# VisSleepSchema.net
KiCad netlist of a schematic drawn in EAGLE
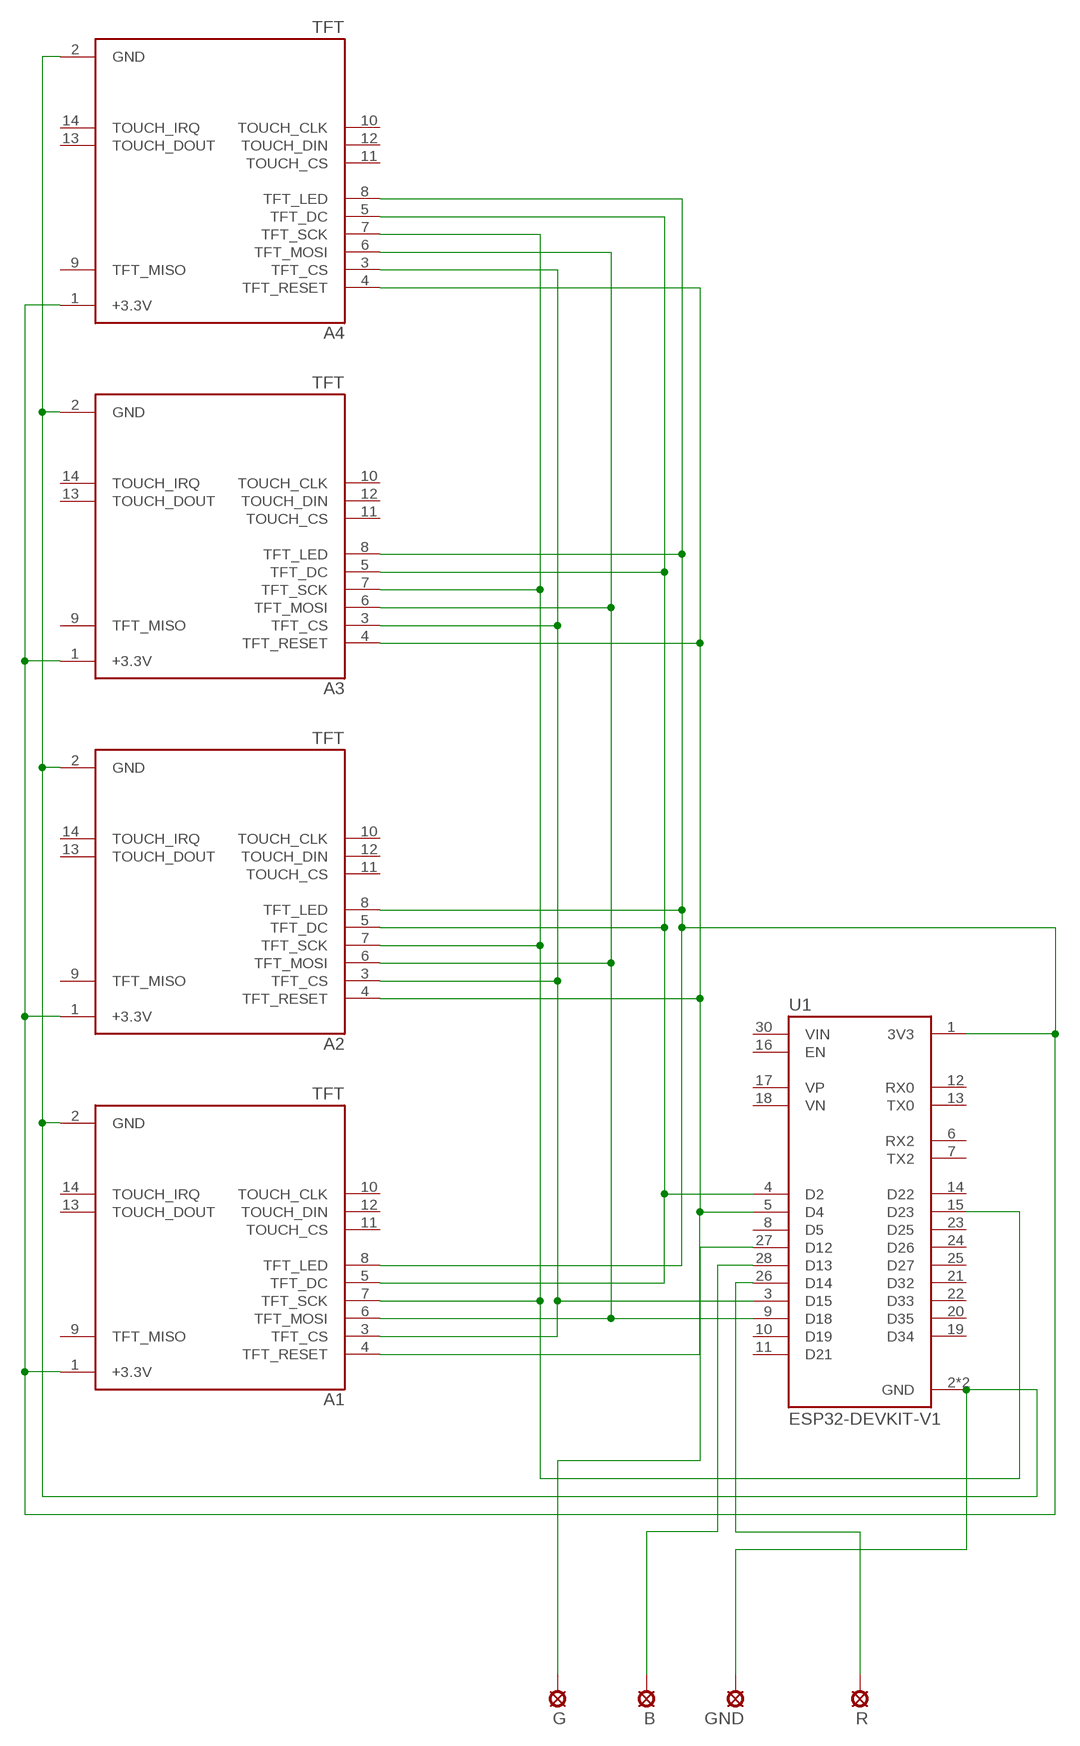
[diagram p0: schematic, sheet 1]

(export (version "E")
  (design (tool "Eeschema 10.0.6"))
  (components
    (comp (ref "A1")
      (value "TFT")
      (footprint "eagle-import:2.8_LCD")
      (libsource (lib "eagle-import") (part "TFT"))
    )
    (comp (ref "A2")
      (value "TFT")
      (footprint "eagle-import:2.8_LCD")
      (libsource (lib "eagle-import") (part "TFT"))
    )
    (comp (ref "A3")
      (value "TFT")
      (footprint "eagle-import:2.8_LCD")
      (libsource (lib "eagle-import") (part "TFT"))
    )
    (comp (ref "A4")
      (value "TFT")
      (footprint "eagle-import:2.8_LCD")
      (libsource (lib "eagle-import") (part "TFT"))
    )
    (comp (ref "B")
      (value "LSP10")
      (footprint "eagle-import:LSP10")
      (libsource (lib "eagle-import") (part "LSP10"))
    )
    (comp (ref "G")
      (value "LSP10")
      (footprint "eagle-import:LSP10")
      (libsource (lib "eagle-import") (part "LSP10"))
    )
    (comp (ref "GND")
      (value "LSP10")
      (footprint "eagle-import:LSP10")
      (libsource (lib "eagle-import") (part "LSP10"))
    )
    (comp (ref "R")
      (value "LSP10")
      (footprint "eagle-import:LSP10")
      (libsource (lib "eagle-import") (part "LSP10"))
    )
    (comp (ref "U1")
      (value "ESP32-DEVKIT-V1")
      (footprint "eagle-import:MODULE_ESP32_DEVKIT_V1")
      (fields (field (name "MF") "Do it"))
      (libsource (lib "eagle-import") (part "ESP32-DEVKIT-V1"))
    )
  )
  (nets
    (net (code "1") (name "Net-(A1-+3.3V)") (class "Default")
      (node (ref "A1") (pin "1") (pinfunction "+3.3V_1") (pintype "passive"))
      (node (ref "A1") (pin "8") (pinfunction "TFT_LED_8") (pintype "input"))
      (node (ref "A2") (pin "1") (pinfunction "+3.3V_1") (pintype "passive"))
      (node (ref "A2") (pin "8") (pinfunction "TFT_LED_8") (pintype "input"))
      (node (ref "A3") (pin "1") (pinfunction "+3.3V_1") (pintype "passive"))
      (node (ref "A3") (pin "8") (pinfunction "TFT_LED_8") (pintype "input"))
      (node (ref "A4") (pin "1") (pinfunction "+3.3V_1") (pintype "passive"))
      (node (ref "A4") (pin "8") (pinfunction "TFT_LED_8") (pintype "input"))
      (node (ref "U1") (pin "1") (pinfunction "3V3_1") (pintype "output"))
    )
    (net (code "2") (name "Net-(A1-GND)") (class "Default")
      (node (ref "A1") (pin "2") (pinfunction "GND_2") (pintype "passive"))
      (node (ref "A2") (pin "2") (pinfunction "GND_2") (pintype "passive"))
      (node (ref "A3") (pin "2") (pinfunction "GND_2") (pintype "passive"))
      (node (ref "A4") (pin "2") (pinfunction "GND_2") (pintype "passive"))
      (node (ref "GND") (pin "MP") (pinfunction "MP_MP") (pintype "passive"))
      (node (ref "U1") (pin "2") (pinfunction "GND_2") (pintype "power_in"))
      (node (ref "U1") (pin "29") (pinfunction "GND_29") (pintype "power_in"))
    )
    (net (code "3") (name "Net-(A1-TFT_CS)") (class "Default")
      (node (ref "A1") (pin "3") (pinfunction "TFT_CS_3") (pintype "input"))
      (node (ref "A2") (pin "3") (pinfunction "TFT_CS_3") (pintype "input"))
      (node (ref "A3") (pin "3") (pinfunction "TFT_CS_3") (pintype "input"))
      (node (ref "A4") (pin "3") (pinfunction "TFT_CS_3") (pintype "input"))
      (node (ref "U1") (pin "3") (pinfunction "D15_3") (pintype "bidirectional"))
    )
    (net (code "4") (name "Net-(A1-TFT_DC)") (class "Default")
      (node (ref "A1") (pin "5") (pinfunction "TFT_DC_5") (pintype "input"))
      (node (ref "A2") (pin "5") (pinfunction "TFT_DC_5") (pintype "input"))
      (node (ref "A3") (pin "5") (pinfunction "TFT_DC_5") (pintype "input"))
      (node (ref "A4") (pin "5") (pinfunction "TFT_DC_5") (pintype "input"))
      (node (ref "U1") (pin "4") (pinfunction "D2_4") (pintype "bidirectional"))
    )
    (net (code "5") (name "Net-(A1-TFT_MOSI)") (class "Default")
      (node (ref "A1") (pin "6") (pinfunction "TFT_MOSI_6") (pintype "input"))
      (node (ref "A2") (pin "6") (pinfunction "TFT_MOSI_6") (pintype "input"))
      (node (ref "A3") (pin "6") (pinfunction "TFT_MOSI_6") (pintype "input"))
      (node (ref "A4") (pin "6") (pinfunction "TFT_MOSI_6") (pintype "input"))
      (node (ref "U1") (pin "9") (pinfunction "D18_9") (pintype "bidirectional"))
    )
    (net (code "6") (name "Net-(A1-TFT_RESET)") (class "Default")
      (node (ref "A1") (pin "4") (pinfunction "TFT_RESET_4") (pintype "input"))
      (node (ref "A2") (pin "4") (pinfunction "TFT_RESET_4") (pintype "input"))
      (node (ref "A3") (pin "4") (pinfunction "TFT_RESET_4") (pintype "input"))
      (node (ref "A4") (pin "4") (pinfunction "TFT_RESET_4") (pintype "input"))
      (node (ref "U1") (pin "5") (pinfunction "D4_5") (pintype "bidirectional"))
    )
    (net (code "7") (name "Net-(A1-TFT_SCK)") (class "Default")
      (node (ref "A1") (pin "7") (pinfunction "TFT_SCK_7") (pintype "input"))
      (node (ref "A2") (pin "7") (pinfunction "TFT_SCK_7") (pintype "input"))
      (node (ref "A3") (pin "7") (pinfunction "TFT_SCK_7") (pintype "input"))
      (node (ref "A4") (pin "7") (pinfunction "TFT_SCK_7") (pintype "input"))
      (node (ref "U1") (pin "15") (pinfunction "D23_15") (pintype "bidirectional"))
    )
    (net (code "8") (name "Net-(U1-D12)") (class "Default")
      (node (ref "G") (pin "MP") (pinfunction "MP_MP") (pintype "passive"))
      (node (ref "U1") (pin "27") (pinfunction "D12_27") (pintype "bidirectional"))
    )
    (net (code "9") (name "Net-(U1-D13)") (class "Default")
      (node (ref "B") (pin "MP") (pinfunction "MP_MP") (pintype "passive"))
      (node (ref "U1") (pin "28") (pinfunction "D13_28") (pintype "bidirectional"))
    )
    (net (code "10") (name "Net-(U1-D14)") (class "Default")
      (node (ref "R") (pin "MP") (pinfunction "MP_MP") (pintype "passive"))
      (node (ref "U1") (pin "26") (pinfunction "D14_26") (pintype "bidirectional"))
    )
    (net (code "11") (name "unconnected-(A1-TFT_MISO-Pad9)") (class "Default")
      (node (ref "A1") (pin "9") (pinfunction "TFT_MISO_9") (pintype "tri_state"))
    )
    (net (code "12") (name "unconnected-(A1-TOUCH_CLK-Pad10)") (class "Default")
      (node (ref "A1") (pin "10") (pinfunction "TOUCH_CLK_10") (pintype "input"))
    )
    (net (code "13") (name "unconnected-(A1-TOUCH_CS-Pad11)") (class "Default")
      (node (ref "A1") (pin "11") (pinfunction "TOUCH_CS_11") (pintype "input"))
    )
    (net (code "14") (name "unconnected-(A1-TOUCH_DIN-Pad12)") (class "Default")
      (node (ref "A1") (pin "12") (pinfunction "TOUCH_DIN_12") (pintype "input"))
    )
    (net (code "15") (name "unconnected-(A1-TOUCH_DOUT-Pad13)") (class "Default")
      (node (ref "A1") (pin "13") (pinfunction "TOUCH_DOUT_13") (pintype "tri_state"))
    )
    (net (code "16") (name "unconnected-(A1-TOUCH_IRQ-Pad14)") (class "Default")
      (node (ref "A1") (pin "14") (pinfunction "TOUCH_IRQ_14") (pintype "open_collector"))
    )
    (net (code "17") (name "unconnected-(A2-TFT_MISO-Pad9)") (class "Default")
      (node (ref "A2") (pin "9") (pinfunction "TFT_MISO_9") (pintype "tri_state"))
    )
    (net (code "18") (name "unconnected-(A2-TOUCH_CLK-Pad10)") (class "Default")
      (node (ref "A2") (pin "10") (pinfunction "TOUCH_CLK_10") (pintype "input"))
    )
    (net (code "19") (name "unconnected-(A2-TOUCH_CS-Pad11)") (class "Default")
      (node (ref "A2") (pin "11") (pinfunction "TOUCH_CS_11") (pintype "input"))
    )
    (net (code "20") (name "unconnected-(A2-TOUCH_DIN-Pad12)") (class "Default")
      (node (ref "A2") (pin "12") (pinfunction "TOUCH_DIN_12") (pintype "input"))
    )
    (net (code "21") (name "unconnected-(A2-TOUCH_DOUT-Pad13)") (class "Default")
      (node (ref "A2") (pin "13") (pinfunction "TOUCH_DOUT_13") (pintype "tri_state"))
    )
    (net (code "22") (name "unconnected-(A2-TOUCH_IRQ-Pad14)") (class "Default")
      (node (ref "A2") (pin "14") (pinfunction "TOUCH_IRQ_14") (pintype "open_collector"))
    )
    (net (code "23") (name "unconnected-(A3-TFT_MISO-Pad9)") (class "Default")
      (node (ref "A3") (pin "9") (pinfunction "TFT_MISO_9") (pintype "tri_state"))
    )
    (net (code "24") (name "unconnected-(A3-TOUCH_CLK-Pad10)") (class "Default")
      (node (ref "A3") (pin "10") (pinfunction "TOUCH_CLK_10") (pintype "input"))
    )
    (net (code "25") (name "unconnected-(A3-TOUCH_CS-Pad11)") (class "Default")
      (node (ref "A3") (pin "11") (pinfunction "TOUCH_CS_11") (pintype "input"))
    )
    (net (code "26") (name "unconnected-(A3-TOUCH_DIN-Pad12)") (class "Default")
      (node (ref "A3") (pin "12") (pinfunction "TOUCH_DIN_12") (pintype "input"))
    )
    (net (code "27") (name "unconnected-(A3-TOUCH_DOUT-Pad13)") (class "Default")
      (node (ref "A3") (pin "13") (pinfunction "TOUCH_DOUT_13") (pintype "tri_state"))
    )
    (net (code "28") (name "unconnected-(A3-TOUCH_IRQ-Pad14)") (class "Default")
      (node (ref "A3") (pin "14") (pinfunction "TOUCH_IRQ_14") (pintype "open_collector"))
    )
    (net (code "29") (name "unconnected-(A4-TFT_MISO-Pad9)") (class "Default")
      (node (ref "A4") (pin "9") (pinfunction "TFT_MISO_9") (pintype "tri_state"))
    )
    (net (code "30") (name "unconnected-(A4-TOUCH_CLK-Pad10)") (class "Default")
      (node (ref "A4") (pin "10") (pinfunction "TOUCH_CLK_10") (pintype "input"))
    )
    (net (code "31") (name "unconnected-(A4-TOUCH_CS-Pad11)") (class "Default")
      (node (ref "A4") (pin "11") (pinfunction "TOUCH_CS_11") (pintype "input"))
    )
    (net (code "32") (name "unconnected-(A4-TOUCH_DIN-Pad12)") (class "Default")
      (node (ref "A4") (pin "12") (pinfunction "TOUCH_DIN_12") (pintype "input"))
    )
    (net (code "33") (name "unconnected-(A4-TOUCH_DOUT-Pad13)") (class "Default")
      (node (ref "A4") (pin "13") (pinfunction "TOUCH_DOUT_13") (pintype "tri_state"))
    )
    (net (code "34") (name "unconnected-(A4-TOUCH_IRQ-Pad14)") (class "Default")
      (node (ref "A4") (pin "14") (pinfunction "TOUCH_IRQ_14") (pintype "open_collector"))
    )
    (net (code "35") (name "unconnected-(U1-D5-Pad8)") (class "Default")
      (node (ref "U1") (pin "8") (pinfunction "D5_8") (pintype "bidirectional"))
    )
    (net (code "36") (name "unconnected-(U1-D19-Pad10)") (class "Default")
      (node (ref "U1") (pin "10") (pinfunction "D19_10") (pintype "bidirectional"))
    )
    (net (code "37") (name "unconnected-(U1-D21-Pad11)") (class "Default")
      (node (ref "U1") (pin "11") (pinfunction "D21_11") (pintype "bidirectional"))
    )
    (net (code "38") (name "unconnected-(U1-D22-Pad14)") (class "Default")
      (node (ref "U1") (pin "14") (pinfunction "D22_14") (pintype "bidirectional"))
    )
    (net (code "39") (name "unconnected-(U1-D25-Pad23)") (class "Default")
      (node (ref "U1") (pin "23") (pinfunction "D25_23") (pintype "bidirectional"))
    )
    (net (code "40") (name "unconnected-(U1-D26-Pad24)") (class "Default")
      (node (ref "U1") (pin "24") (pinfunction "D26_24") (pintype "bidirectional"))
    )
    (net (code "41") (name "unconnected-(U1-D27-Pad25)") (class "Default")
      (node (ref "U1") (pin "25") (pinfunction "D27_25") (pintype "bidirectional"))
    )
    (net (code "42") (name "unconnected-(U1-D32-Pad21)") (class "Default")
      (node (ref "U1") (pin "21") (pinfunction "D32_21") (pintype "bidirectional"))
    )
    (net (code "43") (name "unconnected-(U1-D33-Pad22)") (class "Default")
      (node (ref "U1") (pin "22") (pinfunction "D33_22") (pintype "bidirectional"))
    )
    (net (code "44") (name "unconnected-(U1-D34-Pad19)") (class "Default")
      (node (ref "U1") (pin "19") (pinfunction "D34_19") (pintype "bidirectional"))
    )
    (net (code "45") (name "unconnected-(U1-D35-Pad20)") (class "Default")
      (node (ref "U1") (pin "20") (pinfunction "D35_20") (pintype "bidirectional"))
    )
    (net (code "46") (name "unconnected-(U1-EN-Pad16)") (class "Default")
      (node (ref "U1") (pin "16") (pinfunction "EN_16") (pintype "input"))
    )
    (net (code "47") (name "unconnected-(U1-RX0-Pad12)") (class "Default")
      (node (ref "U1") (pin "12") (pinfunction "RX0_12") (pintype "input"))
    )
    (net (code "48") (name "unconnected-(U1-RX2-Pad6)") (class "Default")
      (node (ref "U1") (pin "6") (pinfunction "RX2_6") (pintype "input"))
    )
    (net (code "49") (name "unconnected-(U1-TX0-Pad13)") (class "Default")
      (node (ref "U1") (pin "13") (pinfunction "TX0_13") (pintype "output"))
    )
    (net (code "50") (name "unconnected-(U1-TX2-Pad7)") (class "Default")
      (node (ref "U1") (pin "7") (pinfunction "TX2_7") (pintype "output"))
    )
    (net (code "51") (name "unconnected-(U1-VIN-Pad30)") (class "Default")
      (node (ref "U1") (pin "30") (pinfunction "VIN_30") (pintype "input"))
    )
    (net (code "52") (name "unconnected-(U1-VN-Pad18)") (class "Default")
      (node (ref "U1") (pin "18") (pinfunction "VN_18") (pintype "bidirectional"))
    )
    (net (code "53") (name "unconnected-(U1-VP-Pad17)") (class "Default")
      (node (ref "U1") (pin "17") (pinfunction "VP_17") (pintype "bidirectional"))
    )
  )
)
